# CPU.net
KiCad netlist of a schematic drawn in Altium Designer
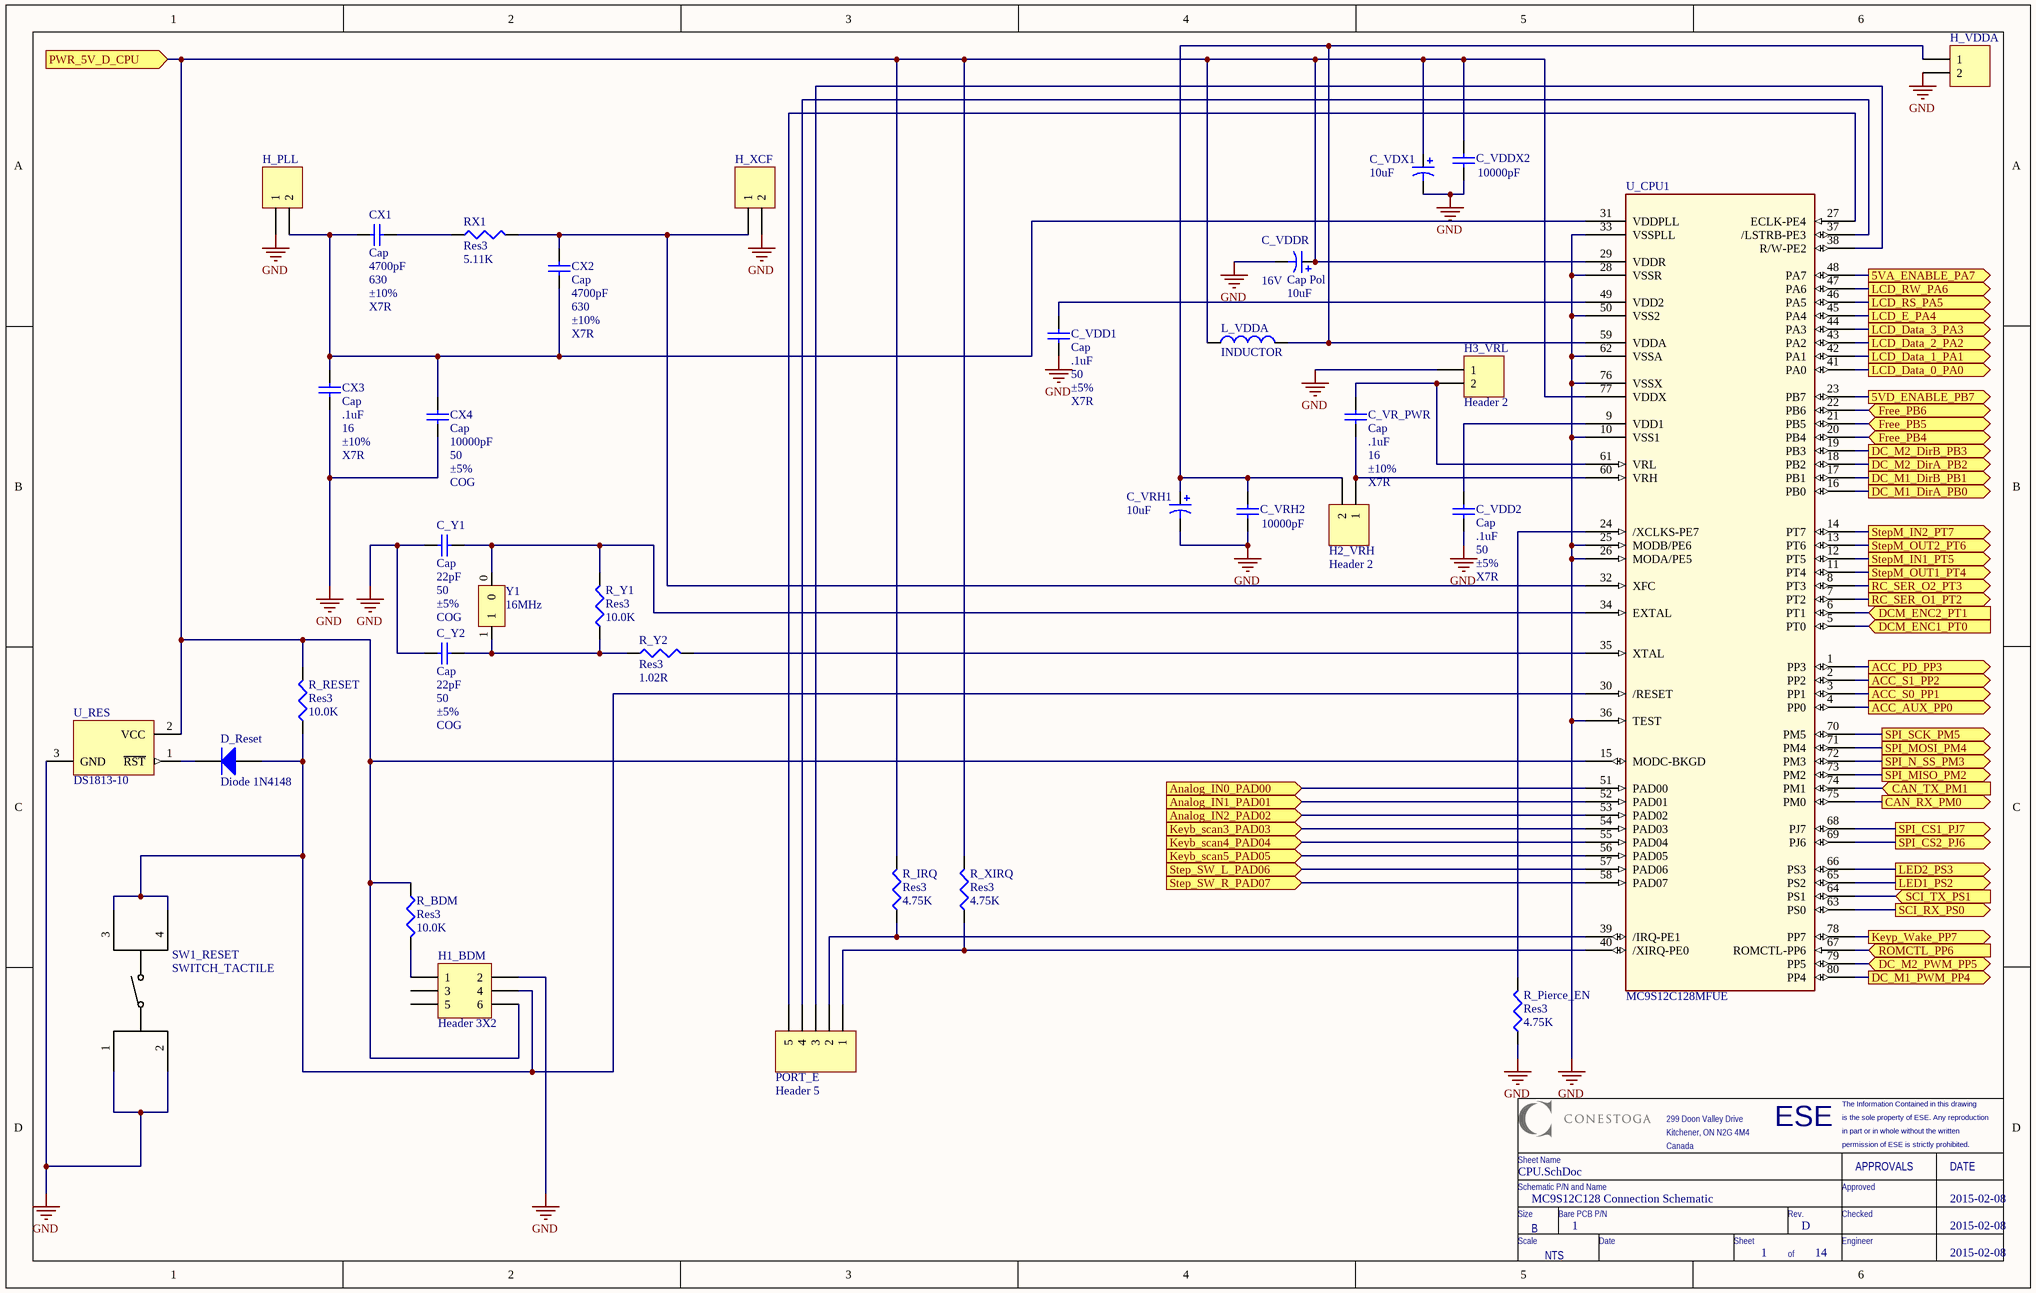
[diagram p0: CPU.SchDoc]

(export (version "E")
  (design (tool "Eeschema 10.0.6"))
  (components
    (comp (ref "CX1")
      (value "Cap")
      (footprint "CAPC2012X09M")
      (description "CAP CER 4700pF 630v X7R 1210")
      (fields
        (field (name "ALTIUM_VALUE") "4700pF")
        (field (name "WV") "630")
        (field (name "TOLERANCE") "±10%")
        (field (name "TYPE") "X7R")
        (field (name "MPN") "C1210C472KBRACTU")
      )
      (libsource (lib "esd_library") (part "CAP-X7R-4700pF-630V-±10%"))
    )
    (comp (ref "CX2")
      (value "Cap")
      (footprint "CAPC2012X09M")
      (description "CAP CER 4700pF 630v X7R 1210")
      (fields
        (field (name "ALTIUM_VALUE") "4700pF")
        (field (name "WV") "630")
        (field (name "TOLERANCE") "±10%")
        (field (name "TYPE") "X7R")
        (field (name "MPN") "C1210C472KBRACTU")
      )
      (libsource (lib "esd_library") (part "CAP-X7R-4700pF-630V-±10%"))
    )
    (comp (ref "CX3")
      (value "Cap")
      (footprint "CAPC2012X09M")
      (description "CAP CER .1uF 16v X7R 0805")
      (fields
        (field (name "ALTIUM_VALUE") ".1uF")
        (field (name "WV") "16")
        (field (name "TOLERANCE") "±10%")
        (field (name "TYPE") "X7R")
        (field (name "MPN") "C0805C104K4RACTU")
      )
      (libsource (lib "esd_library") (part "CAP-X7R-.1uF-16V-±10%"))
    )
    (comp (ref "CX4")
      (value "Cap")
      (footprint "CAPC2012X09M")
      (description "CAP CER 10000pF 50v COG 1210")
      (fields
        (field (name "ALTIUM_VALUE") "10000pF")
        (field (name "WV") "50")
        (field (name "TOLERANCE") "±5%")
        (field (name "TYPE") "COG")
        (field (name "MPN") "C1210C103J5GACTU")
      )
      (libsource (lib "esd_library") (part "CAP-COG-10000pF-50V-±5%"))
    )
    (comp (ref "C_VDD1")
      (value "Cap")
      (footprint "CAPC2012X09M")
      (description "CAP CER .1uF 50v X7R 0805")
      (fields
        (field (name "ALTIUM_VALUE") ".1uF")
        (field (name "WV") "50")
        (field (name "TOLERANCE") "±5%")
        (field (name "TYPE") "X7R")
        (field (name "MPN") "C0805C104J5RACTU")
      )
      (libsource (lib "esd_library") (part "CAP-X7R-.1uF-50V-±5%"))
    )
    (comp (ref "C_VDD2")
      (value "Cap")
      (footprint "CAPC2012X09M")
      (description "CAP CER .1uF 50v X7R 0805")
      (fields
        (field (name "ALTIUM_VALUE") ".1uF")
        (field (name "WV") "50")
        (field (name "TOLERANCE") "±5%")
        (field (name "TYPE") "X7R")
        (field (name "MPN") "C0805C104J5RACTU")
      )
      (libsource (lib "esd_library") (part "CAP-X7R-.1uF-50V-±5%"))
    )
    (comp (ref "C_VDDR")
      (value "Cap Pol")
      (footprint "CAPACITOR_3MM")
      (description "CAP 85C 10uF ±20% 16V WX Series Aluminum Electrolytic")
      (fields
        (field (name "ALTIUM_VALUE") "10uF")
        (field (name "VOLTAGE") "16V")
        (field (name "MPN") "UWX1C100MCL2GB")
      )
      (libsource (lib "esd_library") (part "Cap Polar-10uF-16V"))
    )
    (comp (ref "C_VDDX2")
      (value "10000pF")
      (footprint "CAPC2012X09M")
      (description "CAP CER 10000pF 50v X7R 0805")
      (fields (field (name "TOLERANCE") "±10%") (field (name "MPN") "C0805C103K5RACTU"))
      (libsource (lib "esd_library") (part "CAP-X7R-10000pF-50V-±10%"))
    )
    (comp (ref "C_VDX1")
      (value "10uF")
      (footprint "CAPACITOR_3MM")
      (description "CAP 85C 10uF ±20% 16V WX Series Aluminum Electrolytic")
      (fields (field (name "VOLTAGE") "16V") (field (name "MPN") "UWX1C100MCL2GB"))
      (libsource (lib "esd_library") (part "Cap Polar-10uF-16V"))
    )
    (comp (ref "C_VRH1")
      (value "10uF")
      (footprint "CAPACITOR_3MM")
      (description "CAP 85C 10uF ±20% 16V WX Series Aluminum Electrolytic")
      (fields (field (name "VOLTAGE") "16V") (field (name "MPN") "UWX1C100MCL2GB"))
      (libsource (lib "esd_library") (part "Cap Polar-10uF-16V"))
    )
    (comp (ref "C_VRH2")
      (value "10000pF")
      (footprint "CAPC2012X09M")
      (description "CAP CER 10000pF 50v X7R 0805")
      (fields (field (name "TOLERANCE") "±10%") (field (name "MPN") "C0805C103K5RACTU"))
      (libsource (lib "esd_library") (part "CAP-X7R-10000pF-50V-±10%"))
    )
    (comp (ref "C_VR_PWR")
      (value "Cap")
      (footprint "CAPC2012X09M")
      (description "CAP CER .1uF 16v X7R 0805")
      (fields
        (field (name "ALTIUM_VALUE") ".1uF")
        (field (name "WV") "16")
        (field (name "TOLERANCE") "±10%")
        (field (name "TYPE") "X7R")
        (field (name "MPN") "C0805C104K4RACTU")
      )
      (libsource (lib "esd_library") (part "CAP-X7R-.1uF-16V-±10%"))
    )
    (comp (ref "C_Y1")
      (value "Cap")
      (footprint "CAPC2012X09M")
      (description "CAP CER 22pF 50v COG 0805")
      (fields
        (field (name "ALTIUM_VALUE") "22pF")
        (field (name "WV") "50")
        (field (name "TOLERANCE") "±5%")
        (field (name "TYPE") "COG")
        (field (name "MPN") "C0805C220J5GACTU")
      )
      (libsource (lib "esd_library") (part "CAP-COG-22pF-50V-±5%"))
    )
    (comp (ref "C_Y2")
      (value "Cap")
      (footprint "CAPC2012X09M")
      (description "CAP CER 22pF 50v COG 0805")
      (fields
        (field (name "ALTIUM_VALUE") "22pF")
        (field (name "WV") "50")
        (field (name "TOLERANCE") "±5%")
        (field (name "TYPE") "COG")
        (field (name "MPN") "C0805C220J5GACTU")
      )
      (libsource (lib "esd_library") (part "CAP-COG-22pF-50V-±5%"))
    )
    (comp (ref "D_Reset")
      (value "Diode 1N4148")
      (footprint "zener_sod323")
      (description "High Conductance Fast Diode")
      (fields (field (name "MPN") "1N4148WX-TP"))
      (libsource (lib "esd_library") (part "Diode 1N4148"))
    )
    (comp (ref "H1_BDM")
      (value "Header 3X2")
      (footprint "HDR2X3")
      (description "Header, 3-Pin, Dual row")
      (fields (field (name "PUBLISHER") "Altium Limited"))
      (libsource (lib "Miscellaneous Connectors") (part "Header 3X2"))
    )
    (comp (ref "H2_VRH")
      (value "Header 2")
      (footprint "HDR1X2")
      (description "Header, 2-Pin")
      (fields (field (name "MPN") "PEC02SFAN"))
      (libsource (lib "") (part "Header 2_2"))
    )
    (comp (ref "H3_VRL")
      (value "Header 2")
      (footprint "HDR1X2")
      (description "Header, 2-Pin")
      (fields (field (name "MPN") "PEC02SFAN"))
      (libsource (lib "esd_library") (part "Header 2"))
    )
    (comp (ref "H_PLL")
      (value "Header 2")
      (footprint "HDR1X2")
      (description "Header, 2-Pin")
      (fields (field (name "MPN") "PEC02SFAN"))
      (libsource (lib "") (part "Header 2_1"))
    )
    (comp (ref "H_VDDA")
      (value "Header 2")
      (footprint "HDR1X2")
      (description "Header, 2-Pin")
      (fields (field (name "MPN") "PEC02SFAN"))
      (libsource (lib "esd_library") (part "Header 2"))
    )
    (comp (ref "H_XCF")
      (value "Header 2")
      (footprint "HDR1X2")
      (description "Header, 2-Pin")
      (fields (field (name "MPN") "PEC02SFAN"))
      (libsource (lib "") (part "Header 2_1"))
    )
    (comp (ref "L_VDDA")
      (value "INDUCTOR")
      (footprint "C1210")
      (libsource (lib "esd_library") (part "INDUCTOR"))
    )
    (comp (ref "PORT_E")
      (value "Header 5")
      (footprint "HDR1X5")
      (description "Header, 5-Pin")
      (fields (field (name "MPN") "PEC05SFAN"))
      (libsource (lib "esd_library") (part "Header 5"))
    )
    (comp (ref "RX1")
      (value "Res3")
      (footprint "RESC2112X05M")
      (description "RES SMD 5.11K OHM 1% 1/8W 0805")
      (fields (field (name "ALTIUM_VALUE") "5.11K") (field (name "MPN") "CRCW08055K11FKEA"))
      (libsource (lib "esd_library") (part "Resistor_5.11K"))
    )
    (comp (ref "R_BDM")
      (value "Res3")
      (footprint "RESC2112X05M")
      (description "RES SMD 10.0K OHM 1% 1/8W 0805")
      (fields (field (name "ALTIUM_VALUE") "10.0K") (field (name "MPN") "CRCW080510K0FKEA"))
      (libsource (lib "esd_library") (part "Resistor_10.0K"))
    )
    (comp (ref "R_IRQ")
      (value "Res3")
      (footprint "RESC2112X05M")
      (description "RES SMD 4.75K OHM 1% 1/8W 0805")
      (fields (field (name "ALTIUM_VALUE") "4.75K") (field (name "MPN") "CRCW08054K75FKEA"))
      (libsource (lib "esd_library") (part "Resistor_4.75K"))
    )
    (comp (ref "R_Pierce_EN")
      (value "Res3")
      (footprint "RESC2112X05M")
      (description "RES SMD 4.75K OHM 1% 1/8W 0805")
      (fields (field (name "ALTIUM_VALUE") "4.75K") (field (name "MPN") "CRCW08054K75FKEA"))
      (libsource (lib "esd_library") (part "Resistor_4.75K"))
    )
    (comp (ref "R_RESET")
      (value "Res3")
      (footprint "RESC2112X05M")
      (description "RES SMD 10.0K OHM 1% 1/8W 0805")
      (fields (field (name "ALTIUM_VALUE") "10.0K") (field (name "MPN") "CRCW080510K0FKEA"))
      (libsource (lib "esd_library") (part "Resistor_10.0K"))
    )
    (comp (ref "R_XIRQ")
      (value "Res3")
      (footprint "RESC2112X05M")
      (description "RES SMD 4.75K OHM 1% 1/8W 0805")
      (fields (field (name "ALTIUM_VALUE") "4.75K") (field (name "MPN") "CRCW08054K75FKEA"))
      (libsource (lib "esd_library") (part "Resistor_4.75K"))
    )
    (comp (ref "R_Y1")
      (value "Res3")
      (footprint "RESC2112X05M")
      (description "RES SMD 10.0K OHM 1% 1/8W 0805")
      (fields (field (name "ALTIUM_VALUE") "10.0K") (field (name "MPN") "CRCW080510K0FKEA"))
      (libsource (lib "esd_library") (part "Resistor_10.0K"))
    )
    (comp (ref "R_Y2")
      (value "Res3")
      (footprint "RESC2112X05M")
      (description "RES SMD 1.02R OHM 1% 1/8W 0805")
      (fields (field (name "ALTIUM_VALUE") "1.02R") (field (name "MPN") "CRCW08051R02FKEA"))
      (libsource (lib "esd_library") (part "Resistor_1.02R"))
    )
    (comp (ref "SW1_RESET")
      (value "SWITCH_TACTILE")
      (footprint "TACT_SWITCH_6MM_SMT")
      (description "SWITCH TACTILE SPST-NO 0.05A 12V")
      (fields (field (name "MPN") "PTS645SH50SMTR92 LFS"))
      (libsource (lib "esd_library") (part "SWITCH_TACTILE"))
    )
    (comp (ref "U_CPU1")
      (value "MC9S12C128MFUE")
      (footprint "QUAD.65M/80/WG17.45-HCS12")
      (description "IC MCU 16BIT 128KB FLASH 80QFP")
      (fields (field (name "MPN") "MC9S12C32CFUE25"))
      (libsource (lib "esd_library") (part "MC9S12C128MFUE"))
    )
    (comp (ref "U_RES")
      (value "DS1813-10")
      (footprint "SOT95P230X110-3M")
      (description "5V EconoReset with Pushbutton")
      (fields (field (name "MPN") "DS1813R-10+T&R") (field (name "PUBLISHER") "Altium Limited"))
      (libsource (lib "esd_library") (part "DS1813-10"))
    )
    (comp (ref "Y1")
      (value "16MHz")
      (footprint "PCBComponent_1")
      (fields (field (name "Comment") "ECS-160-20-5P"))
      (libsource (lib "ECS-160-20-5P") (part "ECS-160-20-5P"))
    )
  )
  (nets
    (net (code "1") (name "/5VA_ENABLE_PA7") (class "Default")
      (node (ref "U_CPU1") (pin "48") (pinfunction "PA7_48") (pintype "bidirectional"))
    )
    (net (code "2") (name "/5VD_ENABLE_PB7") (class "Default")
      (node (ref "U_CPU1") (pin "23") (pinfunction "PB7_23") (pintype "bidirectional"))
    )
    (net (code "3") (name "/ACC_AUX_PP0") (class "Default")
      (node (ref "U_CPU1") (pin "4") (pinfunction "PP0_4") (pintype "bidirectional"))
    )
    (net (code "4") (name "/ACC_PD_PP3") (class "Default")
      (node (ref "U_CPU1") (pin "1") (pinfunction "PP3_1") (pintype "bidirectional"))
    )
    (net (code "5") (name "/ACC_S0_PP1") (class "Default")
      (node (ref "U_CPU1") (pin "3") (pinfunction "PP1_3") (pintype "bidirectional"))
    )
    (net (code "6") (name "/ACC_S1_PP2") (class "Default")
      (node (ref "U_CPU1") (pin "2") (pinfunction "PP2_2") (pintype "bidirectional"))
    )
    (net (code "7") (name "/Analog_IN0_PAD00") (class "Default")
      (node (ref "U_CPU1") (pin "51") (pinfunction "PAD00_51") (pintype "input"))
    )
    (net (code "8") (name "/Analog_IN1_PAD01") (class "Default")
      (node (ref "U_CPU1") (pin "52") (pinfunction "PAD01_52") (pintype "input"))
    )
    (net (code "9") (name "/Analog_IN2_PAD02") (class "Default")
      (node (ref "U_CPU1") (pin "53") (pinfunction "PAD02_53") (pintype "input"))
    )
    (net (code "10") (name "/CAN_RX_PM0") (class "Default")
      (node (ref "U_CPU1") (pin "75") (pinfunction "PM0_75") (pintype "bidirectional"))
    )
    (net (code "11") (name "/CAN_TX_PM1") (class "Default")
      (node (ref "U_CPU1") (pin "74") (pinfunction "PM1_74") (pintype "bidirectional"))
    )
    (net (code "12") (name "/DCM_ENC1_PT0") (class "Default")
      (node (ref "U_CPU1") (pin "5") (pinfunction "PT0_5") (pintype "bidirectional"))
    )
    (net (code "13") (name "/DCM_ENC2_PT1") (class "Default")
      (node (ref "U_CPU1") (pin "6") (pinfunction "PT1_6") (pintype "bidirectional"))
    )
    (net (code "14") (name "/DC_M1_DirA_PB0") (class "Default")
      (node (ref "U_CPU1") (pin "16") (pinfunction "PB0_16") (pintype "bidirectional"))
    )
    (net (code "15") (name "/DC_M1_DirB_PB1") (class "Default")
      (node (ref "U_CPU1") (pin "17") (pinfunction "PB1_17") (pintype "bidirectional"))
    )
    (net (code "16") (name "/DC_M1_PWM_PP4") (class "Default")
      (node (ref "U_CPU1") (pin "80") (pinfunction "PP4_80") (pintype "bidirectional"))
    )
    (net (code "17") (name "/DC_M2_DirA_PB2") (class "Default")
      (node (ref "U_CPU1") (pin "18") (pinfunction "PB2_18") (pintype "bidirectional"))
    )
    (net (code "18") (name "/DC_M2_DirB_PB3") (class "Default")
      (node (ref "U_CPU1") (pin "19") (pinfunction "PB3_19") (pintype "bidirectional"))
    )
    (net (code "19") (name "/DC_M2_PWM_PP5") (class "Default")
      (node (ref "U_CPU1") (pin "79") (pinfunction "PP5_79") (pintype "bidirectional"))
    )
    (net (code "20") (name "/Free_PB4") (class "Default")
      (node (ref "U_CPU1") (pin "20") (pinfunction "PB4_20") (pintype "bidirectional"))
    )
    (net (code "21") (name "/Free_PB5") (class "Default")
      (node (ref "U_CPU1") (pin "21") (pinfunction "PB5_21") (pintype "bidirectional"))
    )
    (net (code "22") (name "/Free_PB6") (class "Default")
      (node (ref "U_CPU1") (pin "22") (pinfunction "PB6_22") (pintype "bidirectional"))
    )
    (net (code "23") (name "/Keyb_scan3_PAD03") (class "Default")
      (node (ref "U_CPU1") (pin "54") (pinfunction "PAD03_54") (pintype "input"))
    )
    (net (code "24") (name "/Keyb_scan4_PAD04") (class "Default")
      (node (ref "U_CPU1") (pin "55") (pinfunction "PAD04_55") (pintype "input"))
    )
    (net (code "25") (name "/Keyb_scan5_PAD05") (class "Default")
      (node (ref "U_CPU1") (pin "56") (pinfunction "PAD05_56") (pintype "input"))
    )
    (net (code "26") (name "/Keyp_Wake_PP7") (class "Default")
      (node (ref "U_CPU1") (pin "78") (pinfunction "PP7_78") (pintype "bidirectional"))
    )
    (net (code "27") (name "/LCD_Data_0_PA0") (class "Default")
      (node (ref "U_CPU1") (pin "41") (pinfunction "PA0_41") (pintype "bidirectional"))
    )
    (net (code "28") (name "/LCD_Data_1_PA1") (class "Default")
      (node (ref "U_CPU1") (pin "42") (pinfunction "PA1_42") (pintype "bidirectional"))
    )
    (net (code "29") (name "/LCD_Data_2_PA2") (class "Default")
      (node (ref "U_CPU1") (pin "43") (pinfunction "PA2_43") (pintype "bidirectional"))
    )
    (net (code "30") (name "/LCD_Data_3_PA3") (class "Default")
      (node (ref "U_CPU1") (pin "44") (pinfunction "PA3_44") (pintype "bidirectional"))
    )
    (net (code "31") (name "/LCD_E_PA4") (class "Default")
      (node (ref "U_CPU1") (pin "45") (pinfunction "PA4_45") (pintype "bidirectional"))
    )
    (net (code "32") (name "/LCD_RS_PA5") (class "Default")
      (node (ref "U_CPU1") (pin "46") (pinfunction "PA5_46") (pintype "bidirectional"))
    )
    (net (code "33") (name "/LCD_RW_PA6") (class "Default")
      (node (ref "U_CPU1") (pin "47") (pinfunction "PA6_47") (pintype "bidirectional"))
    )
    (net (code "34") (name "/LED1_PS2") (class "Default")
      (node (ref "U_CPU1") (pin "65") (pinfunction "PS2_65") (pintype "bidirectional"))
    )
    (net (code "35") (name "/LED2_PS3") (class "Default")
      (node (ref "U_CPU1") (pin "66") (pinfunction "PS3_66") (pintype "bidirectional"))
    )
    (net (code "36") (name "/PWR_5V_D_CPU") (class "Default")
      (node (ref "C_VDDR") (pin "1") (pinfunction "1_1") (pintype "passive"))
      (node (ref "C_VDDX2") (pin "2") (pinfunction "2_2") (pintype "passive"))
      (node (ref "C_VDX1") (pin "1") (pinfunction "1_1") (pintype "passive"))
      (node (ref "H1_BDM") (pin "6") (pinfunction "6_6") (pintype "passive"))
      (node (ref "L_VDDA") (pin "1") (pinfunction "1_1") (pintype "passive"))
      (node (ref "R_BDM") (pin "1") (pinfunction "1_1") (pintype "passive"))
      (node (ref "R_IRQ") (pin "2") (pinfunction "2_2") (pintype "passive"))
      (node (ref "R_RESET") (pin "2") (pinfunction "2_2") (pintype "passive"))
      (node (ref "R_XIRQ") (pin "2") (pinfunction "2_2") (pintype "passive"))
      (node (ref "U_CPU1") (pin "15") (pinfunction "MODC-BKGD_15") (pintype "bidirectional"))
      (node (ref "U_CPU1") (pin "29") (pinfunction "VDDR_29") (pintype "power_in"))
      (node (ref "U_CPU1") (pin "77") (pinfunction "VDDX_77") (pintype "power_in"))
      (node (ref "U_RES") (pin "2") (pinfunction "VCC_2") (pintype "power_in"))
    )
    (net (code "37") (name "/RC_SER_O1_PT2") (class "Default")
      (node (ref "U_CPU1") (pin "7") (pinfunction "PT2_7") (pintype "bidirectional"))
    )
    (net (code "38") (name "/RC_SER_O2_PT3") (class "Default")
      (node (ref "U_CPU1") (pin "8") (pinfunction "PT3_8") (pintype "bidirectional"))
    )
    (net (code "39") (name "/ROMCTL_PP6") (class "Default")
      (node (ref "U_CPU1") (pin "67") (pinfunction "ROMCTL-PP6_67") (pintype "input"))
    )
    (net (code "40") (name "/SCI_RX_PS0") (class "Default")
      (node (ref "U_CPU1") (pin "63") (pinfunction "PS0_63") (pintype "bidirectional"))
    )
    (net (code "41") (name "/SCI_TX_PS1") (class "Default")
      (node (ref "U_CPU1") (pin "64") (pinfunction "PS1_64") (pintype "bidirectional"))
    )
    (net (code "42") (name "/SPI_CS1_PJ7") (class "Default")
      (node (ref "U_CPU1") (pin "68") (pinfunction "PJ7_68") (pintype "bidirectional"))
    )
    (net (code "43") (name "/SPI_CS2_PJ6") (class "Default")
      (node (ref "U_CPU1") (pin "69") (pinfunction "PJ6_69") (pintype "bidirectional"))
    )
    (net (code "44") (name "/SPI_MISO_PM2") (class "Default")
      (node (ref "U_CPU1") (pin "73") (pinfunction "PM2_73") (pintype "bidirectional"))
    )
    (net (code "45") (name "/SPI_MOSI_PM4") (class "Default")
      (node (ref "U_CPU1") (pin "71") (pinfunction "PM4_71") (pintype "bidirectional"))
    )
    (net (code "46") (name "/SPI_N_SS_PM3") (class "Default")
      (node (ref "U_CPU1") (pin "72") (pinfunction "PM3_72") (pintype "bidirectional"))
    )
    (net (code "47") (name "/SPI_SCK_PM5") (class "Default")
      (node (ref "U_CPU1") (pin "70") (pinfunction "PM5_70") (pintype "bidirectional"))
    )
    (net (code "48") (name "/StepM_IN1_PT5") (class "Default")
      (node (ref "U_CPU1") (pin "12") (pinfunction "PT5_12") (pintype "bidirectional"))
    )
    (net (code "49") (name "/StepM_IN2_PT7") (class "Default")
      (node (ref "U_CPU1") (pin "14") (pinfunction "PT7_14") (pintype "bidirectional"))
    )
    (net (code "50") (name "/StepM_OUT1_PT4") (class "Default")
      (node (ref "U_CPU1") (pin "11") (pinfunction "PT4_11") (pintype "bidirectional"))
    )
    (net (code "51") (name "/StepM_OUT2_PT6") (class "Default")
      (node (ref "U_CPU1") (pin "13") (pinfunction "PT6_13") (pintype "bidirectional"))
    )
    (net (code "52") (name "/Step_SW_L_PAD06") (class "Default")
      (node (ref "U_CPU1") (pin "57") (pinfunction "PAD06_57") (pintype "input"))
    )
    (net (code "53") (name "/Step_SW_R_PAD07") (class "Default")
      (node (ref "U_CPU1") (pin "58") (pinfunction "PAD07_58") (pintype "input"))
    )
    (net (code "54") (name "GND") (class "Default")
      (node (ref "CX3") (pin "1") (pinfunction "1_1") (pintype "passive"))
      (node (ref "CX4") (pin "1") (pinfunction "1_1") (pintype "passive"))
      (node (ref "C_VDD1") (pin "1") (pinfunction "1_1") (pintype "passive"))
      (node (ref "C_VDD2") (pin "1") (pinfunction "1_1") (pintype "passive"))
      (node (ref "C_VDDR") (pin "2") (pinfunction "2_2") (pintype "passive"))
      (node (ref "C_VDDX2") (pin "1") (pinfunction "1_1") (pintype "passive"))
      (node (ref "C_VDX1") (pin "2") (pinfunction "2_2") (pintype "passive"))
      (node (ref "C_VRH1") (pin "2") (pinfunction "2_2") (pintype "passive"))
      (node (ref "C_VRH2") (pin "1") (pinfunction "1_1") (pintype "passive"))
      (node (ref "C_Y1") (pin "1") (pinfunction "1_1") (pintype "passive"))
      (node (ref "C_Y2") (pin "1") (pinfunction "1_1") (pintype "passive"))
      (node (ref "H1_BDM") (pin "2") (pinfunction "2_2") (pintype "passive"))
      (node (ref "H3_VRL") (pin "1") (pinfunction "1_1") (pintype "passive"))
      (node (ref "H_PLL") (pin "1") (pinfunction "1_1") (pintype "passive"))
      (node (ref "H_VDDA") (pin "2") (pinfunction "2_2") (pintype "passive"))
      (node (ref "H_XCF") (pin "2") (pinfunction "2_2") (pintype "passive"))
      (node (ref "R_Pierce_EN") (pin "1") (pinfunction "1_1") (pintype "passive"))
      (node (ref "SW1_RESET") (pin "1") (pinfunction "1_1") (pintype "passive"))
      (node (ref "SW1_RESET") (pin "2") (pinfunction "2_2") (pintype "passive"))
      (node (ref "U_CPU1") (pin "10") (pinfunction "VSS1_10") (pintype "power_in"))
      (node (ref "U_CPU1") (pin "25") (pinfunction "MODB/PE6_25") (pintype "input"))
      (node (ref "U_CPU1") (pin "26") (pinfunction "MODA/PE5_26") (pintype "input"))
      (node (ref "U_CPU1") (pin "28") (pinfunction "VSSR_28") (pintype "power_in"))
      (node (ref "U_CPU1") (pin "33") (pinfunction "VSSPLL_33") (pintype "power_in"))
      (node (ref "U_CPU1") (pin "36") (pinfunction "TEST_36") (pintype "input"))
      (node (ref "U_CPU1") (pin "50") (pinfunction "VSS2_50") (pintype "power_in"))
      (node (ref "U_CPU1") (pin "62") (pinfunction "VSSA_62") (pintype "power_in"))
      (node (ref "U_CPU1") (pin "76") (pinfunction "VSSX_76") (pintype "power_in"))
      (node (ref "U_RES") (pin "3") (pinfunction "GND_3") (pintype "power_in"))
    )
    (net (code "55") (name "Net-(CX1-Pad2)") (class "Default")
      (node (ref "CX1") (pin "2") (pinfunction "2_2") (pintype "passive"))
      (node (ref "RX1") (pin "1") (pinfunction "1_1") (pintype "passive"))
    )
    (net (code "56") (name "Net-(C_Y2-Pad2)") (class "Default")
      (node (ref "C_Y2") (pin "2") (pinfunction "2_2") (pintype "passive"))
      (node (ref "R_Y1") (pin "1") (pinfunction "1_1") (pintype "passive"))
      (node (ref "R_Y2") (pin "1") (pinfunction "1_1") (pintype "passive"))
      (node (ref "Y1") (pin "1") (pinfunction "1_1") (pintype "passive"))
    )
    (net (code "57") (name "Net-(H1_BDM-Pad1)") (class "Default")
      (node (ref "H1_BDM") (pin "1") (pinfunction "1_1") (pintype "passive"))
      (node (ref "R_BDM") (pin "2") (pinfunction "2_2") (pintype "passive"))
    )
    (net (code "58") (name "Net-(U_CPU1-ECLK-PE4)") (class "Default")
      (node (ref "PORT_E") (pin "5") (pinfunction "5_5") (pintype "passive"))
      (node (ref "U_CPU1") (pin "27") (pinfunction "ECLK-PE4_27") (pintype "input"))
    )
    (net (code "59") (name "Net-(U_CPU1-EXTAL)") (class "Default")
      (node (ref "C_Y1") (pin "2") (pinfunction "2_2") (pintype "passive"))
      (node (ref "R_Y1") (pin "2") (pinfunction "2_2") (pintype "passive"))
      (node (ref "U_CPU1") (pin "34") (pinfunction "EXTAL_34") (pintype "input"))
      (node (ref "Y1") (pin "0") (pinfunction "0_0") (pintype "passive"))
    )
    (net (code "60") (name "Net-(U_CPU1-R{slash}W-PE2)") (class "Default")
      (node (ref "PORT_E") (pin "3") (pinfunction "3_3") (pintype "passive"))
      (node (ref "U_CPU1") (pin "38") (pinfunction "R/W-PE2_38") (pintype "bidirectional"))
    )
    (net (code "61") (name "Net-(U_CPU1-VDD1)") (class "Default")
      (node (ref "C_VDD2") (pin "2") (pinfunction "2_2") (pintype "passive"))
      (node (ref "U_CPU1") (pin "9") (pinfunction "VDD1_9") (pintype "power_in"))
    )
    (net (code "62") (name "Net-(U_CPU1-VDD2)") (class "Default")
      (node (ref "C_VDD1") (pin "2") (pinfunction "2_2") (pintype "passive"))
      (node (ref "U_CPU1") (pin "49") (pinfunction "VDD2_49") (pintype "power_in"))
    )
    (net (code "63") (name "Net-(U_CPU1-VDDA)") (class "Default")
      (node (ref "C_VRH1") (pin "1") (pinfunction "1_1") (pintype "passive"))
      (node (ref "C_VRH2") (pin "2") (pinfunction "2_2") (pintype "passive"))
      (node (ref "H2_VRH") (pin "2") (pinfunction "2_2") (pintype "passive"))
      (node (ref "H_VDDA") (pin "1") (pinfunction "1_1") (pintype "passive"))
      (node (ref "L_VDDA") (pin "2") (pinfunction "2_2") (pintype "passive"))
      (node (ref "U_CPU1") (pin "59") (pinfunction "VDDA_59") (pintype "power_in"))
    )
    (net (code "64") (name "Net-(U_CPU1-VDDPLL)") (class "Default")
      (node (ref "CX1") (pin "1") (pinfunction "1_1") (pintype "passive"))
      (node (ref "CX2") (pin "1") (pinfunction "1_1") (pintype "passive"))
      (node (ref "CX3") (pin "2") (pinfunction "2_2") (pintype "passive"))
      (node (ref "CX4") (pin "2") (pinfunction "2_2") (pintype "passive"))
      (node (ref "H_PLL") (pin "2") (pinfunction "2_2") (pintype "passive"))
      (node (ref "U_CPU1") (pin "31") (pinfunction "VDDPLL_31") (pintype "power_in"))
    )
    (net (code "65") (name "Net-(U_CPU1-VRH)") (class "Default")
      (node (ref "C_VR_PWR") (pin "1") (pinfunction "1_1") (pintype "passive"))
      (node (ref "H2_VRH") (pin "1") (pinfunction "1_1") (pintype "passive"))
      (node (ref "U_CPU1") (pin "60") (pinfunction "VRH_60") (pintype "input"))
    )
    (net (code "66") (name "Net-(U_CPU1-VRL)") (class "Default")
      (node (ref "C_VR_PWR") (pin "2") (pinfunction "2_2") (pintype "passive"))
      (node (ref "H3_VRL") (pin "2") (pinfunction "2_2") (pintype "passive"))
      (node (ref "U_CPU1") (pin "61") (pinfunction "VRL_61") (pintype "input"))
    )
    (net (code "67") (name "Net-(U_CPU1-XFC)") (class "Default")
      (node (ref "CX2") (pin "2") (pinfunction "2_2") (pintype "passive"))
      (node (ref "H_XCF") (pin "1") (pinfunction "1_1") (pintype "passive"))
      (node (ref "RX1") (pin "2") (pinfunction "2_2") (pintype "passive"))
      (node (ref "U_CPU1") (pin "32") (pinfunction "XFC_32") (pintype "input"))
    )
    (net (code "68") (name "Net-(U_CPU1-XTAL)") (class "Default")
      (node (ref "R_Y2") (pin "2") (pinfunction "2_2") (pintype "passive"))
      (node (ref "U_CPU1") (pin "35") (pinfunction "XTAL_35") (pintype "input"))
    )
    (net (code "69") (name "Net-(U_CPU1-{slash}IRQ-PE1)") (class "Default")
      (node (ref "PORT_E") (pin "2") (pinfunction "2_2") (pintype "passive"))
      (node (ref "R_IRQ") (pin "1") (pinfunction "1_1") (pintype "passive"))
      (node (ref "U_CPU1") (pin "39") (pinfunction "/IRQ-PE1_39") (pintype "bidirectional"))
    )
    (net (code "70") (name "Net-(U_CPU1-{slash}LSTRB-PE3)") (class "Default")
      (node (ref "PORT_E") (pin "4") (pinfunction "4_4") (pintype "passive"))
      (node (ref "U_CPU1") (pin "37") (pinfunction "/LSTRB-PE3_37") (pintype "bidirectional"))
    )
    (net (code "71") (name "Net-(U_CPU1-{slash}RESET)") (class "Default")
      (node (ref "D_Reset") (pin "A") (pinfunction "A_A") (pintype "passive"))
      (node (ref "H1_BDM") (pin "4") (pinfunction "4_4") (pintype "passive"))
      (node (ref "R_RESET") (pin "1") (pinfunction "1_1") (pintype "passive"))
      (node (ref "SW1_RESET") (pin "3") (pinfunction "3_3") (pintype "passive"))
      (node (ref "SW1_RESET") (pin "4") (pinfunction "4_4") (pintype "passive"))
      (node (ref "U_CPU1") (pin "30") (pinfunction "/RESET_30") (pintype "input"))
    )
    (net (code "72") (name "Net-(U_CPU1-{slash}XCLKS-PE7)") (class "Default")
      (node (ref "R_Pierce_EN") (pin "2") (pinfunction "2_2") (pintype "passive"))
      (node (ref "U_CPU1") (pin "24") (pinfunction "/XCLKS-PE7_24") (pintype "input"))
    )
    (net (code "73") (name "Net-(U_CPU1-{slash}XIRQ-PE0)") (class "Default")
      (node (ref "PORT_E") (pin "1") (pinfunction "1_1") (pintype "passive"))
      (node (ref "R_XIRQ") (pin "1") (pinfunction "1_1") (pintype "passive"))
      (node (ref "U_CPU1") (pin "40") (pinfunction "/XIRQ-PE0_40") (pintype "bidirectional"))
    )
    (net (code "74") (name "Net-(U_RES-~{RST})") (class "Default")
      (node (ref "D_Reset") (pin "K") (pinfunction "K_K") (pintype "passive"))
      (node (ref "U_RES") (pin "1") (pinfunction "~{RST}_1") (pintype "output"))
    )
    (net (code "75") (name "unconnected-(H1_BDM-Pad3)") (class "Default")
      (node (ref "H1_BDM") (pin "3") (pinfunction "3_3") (pintype "passive"))
    )
    (net (code "76") (name "unconnected-(H1_BDM-Pad5)") (class "Default")
      (node (ref "H1_BDM") (pin "5") (pinfunction "5_5") (pintype "passive"))
    )
  )
)
